# LPCB227_-_POWER_SUPPLY.net
KiCad netlist of a schematic drawn in Altium Designer
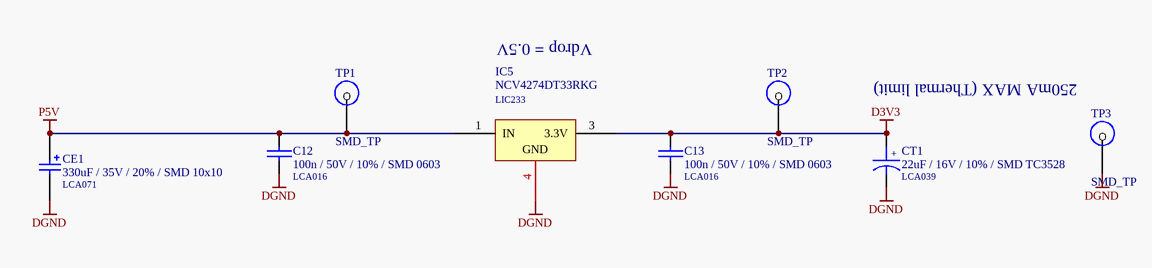
[diagram p0: LPCB227 - POWER SUPPLY.SchDoc]

(export (version "E")
  (design (tool "Eeschema 10.0.6"))
  (components
    (comp (ref "C12")
      (value "100n / 50V / 10% / SMD 0603")
      (footprint "LFP011__CC1608-0603-IPC7351_B")
      (description "Capacitor, Ceramic Chip, 100nF (0.1uF), 50V, 5%, SMD 0603 [LCA016]")
      (fields (field (name "LDL_NUMBER") "LCA016"))
      (libsource (lib "LDL_Capacitors") (part "100n / 50V / 10% / SMD 0603"))
    )
    (comp (ref "C13")
      (value "100n / 50V / 10% / SMD 0603")
      (footprint "LFP011__CC1608-0603-IPC7351_B")
      (description "Capacitor, Ceramic Chip, 100nF (0.1uF), 50V, 5%, SMD 0603 [LCA016]")
      (fields (field (name "LDL_NUMBER") "LCA016"))
      (libsource (lib "LDL_Capacitors") (part "100n / 50V / 10% / SMD 0603"))
    )
    (comp (ref "CE1")
      (value "330uF / 35V / 20% / SMD 10x10")
      (footprint "LFP041__NICHICON_WT_10X10")
      (description "Capacitor, Aluminum Electrolytic, 330uF, 35V, 20%, SMD (10mm x 10mm) [LCA071]")
      (fields (field (name "LDL_NUMBER") "LCA071"))
      (libsource (lib "LDL_Capacitors") (part "330uF / 35V / 20% / SMD 10x10"))
    )
    (comp (ref "CT1")
      (value "22uF / 16V / 10% / SMD TC3528")
      (footprint "LFP018__TC3528")
      (description "Capacitor, Tantalum, 22uF, 16V, 10%, SMD TC3528 (BCASE) [LCA039]")
      (fields (field (name "LDL_NUMBER") "LCA039"))
      (libsource (lib "LDL_Capacitors") (part "22uF / 16V / 10% / SMD TC3528"))
    )
    (comp (ref "IC5")
      (value "NCV4274DT33RKG")
      (footprint "LFP019__369A-13")
      (description "IC, Voltage Regulator, 400mA, 3.3V LDO, SMD DPAK [LIC233]")
      (fields (field (name "LDL_NUMBER") "LIC233"))
      (libsource (lib "LDL_Semiconductors") (part "NCV4274DT33RKG"))
    )
    (comp (ref "TP1")
      (value "SMD_TP")
      (footprint "SMD-TP")
      (description "SMD Test Point")
      (libsource (lib "LDL_Connectors") (part "SMD_TP"))
    )
    (comp (ref "TP2")
      (value "SMD_TP")
      (footprint "SMD-TP")
      (description "SMD Test Point")
      (libsource (lib "LDL_Connectors") (part "SMD_TP"))
    )
    (comp (ref "TP3")
      (value "SMD_TP")
      (footprint "SMD-TP")
      (description "SMD Test Point")
      (libsource (lib "LDL_Connectors") (part "SMD_TP"))
    )
  )
  (nets
    (net (code "1") (name "D3V3") (class "Default")
      (node (ref "C13") (pin "1") (pintype "passive"))
      (node (ref "CT1") (pin "1") (pinfunction "1_1") (pintype "passive"))
      (node (ref "IC5") (pin "3") (pinfunction "3.3V_3") (pintype "power_in"))
      (node (ref "TP2") (pin "1") (pintype "passive"))
    )
    (net (code "2") (name "DGND") (class "Default")
      (node (ref "C12") (pin "2") (pintype "passive"))
      (node (ref "C13") (pin "2") (pintype "passive"))
      (node (ref "CE1") (pin "2") (pinfunction "2_2") (pintype "passive"))
      (node (ref "CT1") (pin "2") (pinfunction "2_2") (pintype "passive"))
      (node (ref "IC5") (pin "4") (pinfunction "GND_4") (pintype "power_in"))
      (node (ref "TP3") (pin "1") (pintype "passive"))
    )
    (net (code "3") (name "P5V") (class "Default")
      (node (ref "C12") (pin "1") (pintype "passive"))
      (node (ref "CE1") (pin "1") (pinfunction "1_1") (pintype "passive"))
      (node (ref "IC5") (pin "1") (pinfunction "IN_1") (pintype "power_in"))
      (node (ref "TP1") (pin "1") (pintype "passive"))
    )
  )
)
